# BQ25504.net
KiCad netlist of a schematic drawn in EAGLE
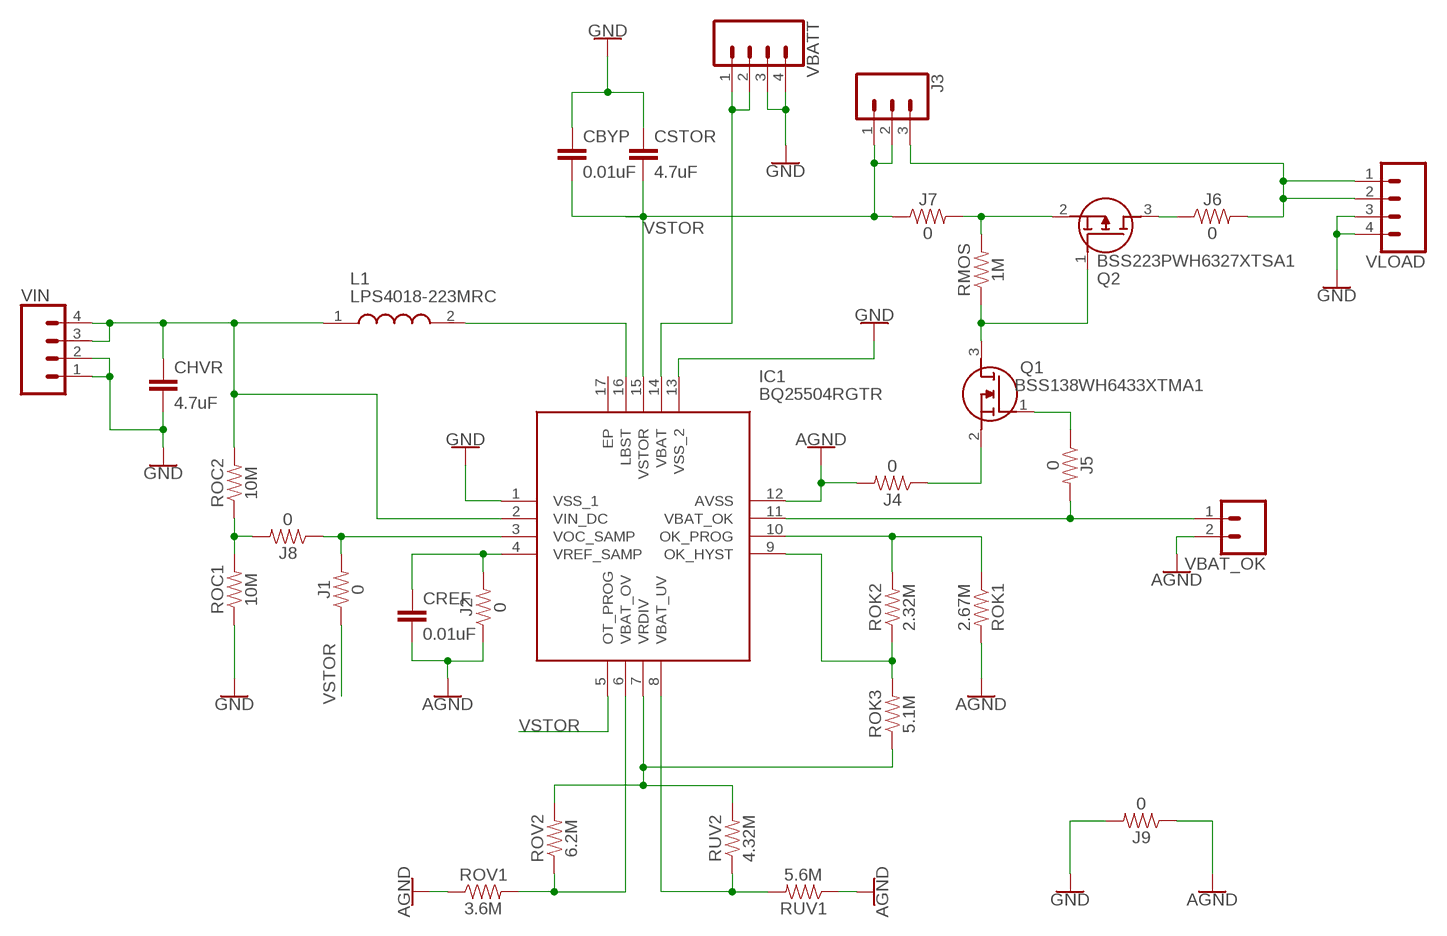
[diagram p0: schematic, sheet 1]

(export (version "E")
  (design (tool "Eeschema 10.0.6"))
  (components
    (comp (ref "CBYP")
      (value "0.01uF")
      (footprint "eagle-import:0603")
      (libsource (lib "eagle-import") (part "CAP-0603"))
    )
    (comp (ref "CHVR")
      (value "4.7uF")
      (footprint "eagle-import:0603")
      (libsource (lib "eagle-import") (part "CAP-0603"))
    )
    (comp (ref "CREF")
      (value "0.01uF")
      (footprint "eagle-import:0603")
      (libsource (lib "eagle-import") (part "CAP-0603"))
    )
    (comp (ref "CSTOR")
      (value "4.7uF")
      (footprint "eagle-import:0603")
      (libsource (lib "eagle-import") (part "CAP-0603"))
    )
    (comp (ref "IC1")
      (value "BQ25504RGTR")
      (footprint "eagle-import:QFN50P300X300X100-17N")
      (fields (field (name "MOUSER_PART_NUMBER") "595-BQ25504RGTR"))
      (libsource (lib "eagle-import") (part "BQ25504RGTR"))
    )
    (comp (ref "J1")
      (value "0")
      (footprint "eagle-import:0402")
      (libsource (lib "eagle-import") (part "RESISTOR0402"))
    )
    (comp (ref "J2")
      (value "0")
      (footprint "eagle-import:0402")
      (libsource (lib "eagle-import") (part "RESISTOR0402"))
    )
    (comp (ref "J3")
      (value "CONN_03")
      (footprint "eagle-import:1X03")
      (libsource (lib "eagle-import") (part "CONN_03"))
    )
    (comp (ref "J4")
      (value "0")
      (footprint "eagle-import:0402")
      (libsource (lib "eagle-import") (part "RESISTOR0402"))
    )
    (comp (ref "J5")
      (value "0")
      (footprint "eagle-import:0402")
      (libsource (lib "eagle-import") (part "RESISTOR0402"))
    )
    (comp (ref "J6")
      (value "0")
      (footprint "eagle-import:0402")
      (libsource (lib "eagle-import") (part "RESISTOR0402"))
    )
    (comp (ref "J7")
      (value "0")
      (footprint "eagle-import:0402")
      (libsource (lib "eagle-import") (part "RESISTOR0402"))
    )
    (comp (ref "J8")
      (value "0")
      (footprint "eagle-import:0402")
      (libsource (lib "eagle-import") (part "RESISTOR0402"))
    )
    (comp (ref "J9")
      (value "0")
      (footprint "eagle-import:0402")
      (libsource (lib "eagle-import") (part "RESISTOR0402"))
    )
    (comp (ref "L1")
      (value "LPS4018-223MRC")
      (footprint "eagle-import:LPS4018223MRC")
      (fields (field (name "MOUSER_PART_NUMBER") "994-LPS4018-223MRC"))
      (libsource (lib "eagle-import") (part "LPS4018-223MRC"))
    )
    (comp (ref "Q1")
      (value "BSS138WH6433XTMA1")
      (footprint "eagle-import:SOT65P210X100-3N")
      (fields (field (name "MOUSER_PART_NUMBER") "726-BSS138WH6433XTMA"))
      (libsource (lib "eagle-import") (part "BSS138WH6433XTMA1"))
    )
    (comp (ref "Q2")
      (value "BSS223PWH6327XTSA1")
      (footprint "eagle-import:SOT65P210X100-3N")
      (fields (field (name "MOUSER_PART_NUMBER") "726-BSS223PWH6327XTS"))
      (libsource (lib "eagle-import") (part "BSS223PWH6327XTSA1"))
    )
    (comp (ref "RMOS")
      (value "1M")
      (footprint "eagle-import:0603")
      (libsource (lib "eagle-import") (part "RESISTOR0603"))
    )
    (comp (ref "ROC1")
      (value "10M")
      (footprint "eagle-import:0603")
      (libsource (lib "eagle-import") (part "RESISTOR0603"))
    )
    (comp (ref "ROC2")
      (value "10M")
      (footprint "eagle-import:0603")
      (libsource (lib "eagle-import") (part "RESISTOR0603"))
    )
    (comp (ref "ROK1")
      (value "2.67M")
      (footprint "eagle-import:0603")
      (libsource (lib "eagle-import") (part "RESISTOR0603"))
    )
    (comp (ref "ROK2")
      (value "2.32M")
      (footprint "eagle-import:0603")
      (libsource (lib "eagle-import") (part "RESISTOR0603"))
    )
    (comp (ref "ROK3")
      (value "5.1M")
      (footprint "eagle-import:0603")
      (libsource (lib "eagle-import") (part "RESISTOR0603"))
    )
    (comp (ref "ROV1")
      (value "3.6M")
      (footprint "eagle-import:0603")
      (libsource (lib "eagle-import") (part "RESISTOR0603"))
    )
    (comp (ref "ROV2")
      (value "6.2M")
      (footprint "eagle-import:0603")
      (libsource (lib "eagle-import") (part "RESISTOR0603"))
    )
    (comp (ref "RUV1")
      (value "5.6M")
      (footprint "eagle-import:0603")
      (libsource (lib "eagle-import") (part "RESISTOR0603"))
    )
    (comp (ref "RUV2")
      (value "4.32M")
      (footprint "eagle-import:0603")
      (libsource (lib "eagle-import") (part "RESISTOR0603"))
    )
    (comp (ref "VBATT")
      (value "CONN_04PTH")
      (footprint "eagle-import:1X04")
      (libsource (lib "eagle-import") (part "CONN_04PTH"))
    )
    (comp (ref "VBAT_OK")
      (value "CONN_02")
      (footprint "eagle-import:1X02")
      (libsource (lib "eagle-import") (part "CONN_02"))
    )
    (comp (ref "VIN")
      (value "CONN_04PTH")
      (footprint "eagle-import:1X04")
      (libsource (lib "eagle-import") (part "CONN_04PTH"))
    )
    (comp (ref "VLOAD")
      (value "CONN_04PTH")
      (footprint "eagle-import:1X04")
      (libsource (lib "eagle-import") (part "CONN_04PTH"))
    )
  )
  (nets
    (net (code "1") (name "/VSTOR") (class "Default")
      (node (ref "CBYP") (pin "2") (pinfunction "2_2") (pintype "passive"))
      (node (ref "CSTOR") (pin "2") (pinfunction "2_2") (pintype "passive"))
      (node (ref "IC1") (pin "15") (pinfunction "VSTOR_15") (pintype "bidirectional"))
      (node (ref "IC1") (pin "5") (pinfunction "OT_PROG_5") (pintype "bidirectional"))
      (node (ref "J1") (pin "1") (pinfunction "1_1") (pintype "passive"))
      (node (ref "J3") (pin "1") (pinfunction "1_1") (pintype "passive"))
      (node (ref "J3") (pin "2") (pinfunction "2_2") (pintype "passive"))
      (node (ref "J7") (pin "1") (pinfunction "1_1") (pintype "passive"))
    )
    (net (code "2") (name "AGND") (class "Default")
      (node (ref "CREF") (pin "2") (pinfunction "2_2") (pintype "passive"))
      (node (ref "IC1") (pin "12") (pinfunction "AVSS_12") (pintype "bidirectional"))
      (node (ref "J2") (pin "1") (pinfunction "1_1") (pintype "passive"))
      (node (ref "J4") (pin "2") (pinfunction "2_2") (pintype "passive"))
      (node (ref "J9") (pin "1") (pinfunction "1_1") (pintype "passive"))
      (node (ref "ROK1") (pin "2") (pinfunction "2_2") (pintype "passive"))
      (node (ref "ROV1") (pin "1") (pinfunction "1_1") (pintype "passive"))
      (node (ref "RUV1") (pin "1") (pinfunction "1_1") (pintype "passive"))
      (node (ref "VBAT_OK") (pin "2") (pinfunction "2_2") (pintype "passive"))
    )
    (net (code "3") (name "GND") (class "Default")
      (node (ref "CBYP") (pin "1") (pinfunction "1_1") (pintype "passive"))
      (node (ref "CHVR") (pin "2") (pinfunction "2_2") (pintype "passive"))
      (node (ref "CSTOR") (pin "1") (pinfunction "1_1") (pintype "passive"))
      (node (ref "IC1") (pin "1") (pinfunction "VSS_1_1") (pintype "bidirectional"))
      (node (ref "IC1") (pin "13") (pinfunction "VSS_2_13") (pintype "bidirectional"))
      (node (ref "J9") (pin "2") (pinfunction "2_2") (pintype "passive"))
      (node (ref "ROC1") (pin "1") (pinfunction "1_1") (pintype "passive"))
      (node (ref "VBATT") (pin "3") (pinfunction "3_3") (pintype "passive"))
      (node (ref "VBATT") (pin "4") (pinfunction "4_4") (pintype "passive"))
      (node (ref "VIN") (pin "1") (pinfunction "1_1") (pintype "passive"))
      (node (ref "VIN") (pin "2") (pinfunction "2_2") (pintype "passive"))
      (node (ref "VLOAD") (pin "3") (pinfunction "3_3") (pintype "passive"))
      (node (ref "VLOAD") (pin "4") (pinfunction "4_4") (pintype "passive"))
    )
    (net (code "4") (name "Net-(IC1-LBST)") (class "Default")
      (node (ref "IC1") (pin "16") (pinfunction "LBST_16") (pintype "bidirectional"))
      (node (ref "L1") (pin "2") (pinfunction "2_2") (pintype "bidirectional"))
    )
    (net (code "5") (name "Net-(IC1-OK_HYST)") (class "Default")
      (node (ref "IC1") (pin "9") (pinfunction "OK_HYST_9") (pintype "bidirectional"))
      (node (ref "ROK2") (pin "1") (pinfunction "1_1") (pintype "passive"))
      (node (ref "ROK3") (pin "2") (pinfunction "2_2") (pintype "passive"))
    )
    (net (code "6") (name "Net-(IC1-OK_PROG)") (class "Default")
      (node (ref "IC1") (pin "10") (pinfunction "OK_PROG_10") (pintype "bidirectional"))
      (node (ref "ROK1") (pin "1") (pinfunction "1_1") (pintype "passive"))
      (node (ref "ROK2") (pin "2") (pinfunction "2_2") (pintype "passive"))
    )
    (net (code "7") (name "Net-(IC1-VBAT)") (class "Default")
      (node (ref "IC1") (pin "14") (pinfunction "VBAT_14") (pintype "bidirectional"))
      (node (ref "VBATT") (pin "1") (pinfunction "1_1") (pintype "passive"))
      (node (ref "VBATT") (pin "2") (pinfunction "2_2") (pintype "passive"))
    )
    (net (code "8") (name "Net-(IC1-VBAT_OK)") (class "Default")
      (node (ref "IC1") (pin "11") (pinfunction "VBAT_OK_11") (pintype "bidirectional"))
      (node (ref "J5") (pin "2") (pinfunction "2_2") (pintype "passive"))
      (node (ref "VBAT_OK") (pin "1") (pinfunction "1_1") (pintype "passive"))
    )
    (net (code "9") (name "Net-(IC1-VBAT_OV)") (class "Default")
      (node (ref "IC1") (pin "6") (pinfunction "VBAT_OV_6") (pintype "bidirectional"))
      (node (ref "ROV1") (pin "2") (pinfunction "2_2") (pintype "passive"))
      (node (ref "ROV2") (pin "1") (pinfunction "1_1") (pintype "passive"))
    )
    (net (code "10") (name "Net-(IC1-VBAT_UV)") (class "Default")
      (node (ref "IC1") (pin "8") (pinfunction "VBAT_UV_8") (pintype "bidirectional"))
      (node (ref "RUV1") (pin "2") (pinfunction "2_2") (pintype "passive"))
      (node (ref "RUV2") (pin "1") (pinfunction "1_1") (pintype "passive"))
    )
    (net (code "11") (name "Net-(IC1-VIN_DC)") (class "Default")
      (node (ref "CHVR") (pin "1") (pinfunction "1_1") (pintype "passive"))
      (node (ref "IC1") (pin "2") (pinfunction "VIN_DC_2") (pintype "bidirectional"))
      (node (ref "L1") (pin "1") (pinfunction "1_1") (pintype "bidirectional"))
      (node (ref "ROC2") (pin "2") (pinfunction "2_2") (pintype "passive"))
      (node (ref "VIN") (pin "3") (pinfunction "3_3") (pintype "passive"))
      (node (ref "VIN") (pin "4") (pinfunction "4_4") (pintype "passive"))
    )
    (net (code "12") (name "Net-(IC1-VOC_SAMP)") (class "Default")
      (node (ref "IC1") (pin "3") (pinfunction "VOC_SAMP_3") (pintype "bidirectional"))
      (node (ref "J1") (pin "2") (pinfunction "2_2") (pintype "passive"))
      (node (ref "J8") (pin "1") (pinfunction "1_1") (pintype "passive"))
    )
    (net (code "13") (name "Net-(IC1-VRDIV)") (class "Default")
      (node (ref "IC1") (pin "7") (pinfunction "VRDIV_7") (pintype "bidirectional"))
      (node (ref "ROK3") (pin "1") (pinfunction "1_1") (pintype "passive"))
      (node (ref "ROV2") (pin "2") (pinfunction "2_2") (pintype "passive"))
      (node (ref "RUV2") (pin "2") (pinfunction "2_2") (pintype "passive"))
    )
    (net (code "14") (name "Net-(IC1-VREF_SAMP)") (class "Default")
      (node (ref "CREF") (pin "1") (pinfunction "1_1") (pintype "passive"))
      (node (ref "IC1") (pin "4") (pinfunction "VREF_SAMP_4") (pintype "bidirectional"))
      (node (ref "J2") (pin "2") (pinfunction "2_2") (pintype "passive"))
    )
    (net (code "15") (name "Net-(J3-Pad3)") (class "Default")
      (node (ref "J3") (pin "3") (pinfunction "3_3") (pintype "passive"))
      (node (ref "J6") (pin "2") (pinfunction "2_2") (pintype "passive"))
      (node (ref "VLOAD") (pin "1") (pinfunction "1_1") (pintype "passive"))
      (node (ref "VLOAD") (pin "2") (pinfunction "2_2") (pintype "passive"))
    )
    (net (code "16") (name "Net-(J8-Pad2)") (class "Default")
      (node (ref "J8") (pin "2") (pinfunction "2_2") (pintype "passive"))
      (node (ref "ROC1") (pin "2") (pinfunction "2_2") (pintype "passive"))
      (node (ref "ROC2") (pin "1") (pinfunction "1_1") (pintype "passive"))
    )
    (net (code "17") (name "Net-(Q1-D)") (class "Default")
      (node (ref "Q1") (pin "3") (pinfunction "D_3") (pintype "bidirectional"))
      (node (ref "Q2") (pin "1") (pinfunction "G_1") (pintype "input"))
      (node (ref "RMOS") (pin "1") (pinfunction "1_1") (pintype "passive"))
    )
    (net (code "18") (name "Net-(Q1-G)") (class "Default")
      (node (ref "J5") (pin "1") (pinfunction "1_1") (pintype "passive"))
      (node (ref "Q1") (pin "1") (pinfunction "G_1") (pintype "bidirectional"))
    )
    (net (code "19") (name "Net-(Q1-S)") (class "Default")
      (node (ref "J4") (pin "1") (pinfunction "1_1") (pintype "passive"))
      (node (ref "Q1") (pin "2") (pinfunction "S_2") (pintype "bidirectional"))
    )
    (net (code "20") (name "Net-(Q2-D)") (class "Default")
      (node (ref "J6") (pin "1") (pinfunction "1_1") (pintype "passive"))
      (node (ref "Q2") (pin "3") (pinfunction "D_3") (pintype "bidirectional"))
    )
    (net (code "21") (name "Net-(Q2-S)") (class "Default")
      (node (ref "J7") (pin "2") (pinfunction "2_2") (pintype "passive"))
      (node (ref "Q2") (pin "2") (pinfunction "S_2") (pintype "bidirectional"))
      (node (ref "RMOS") (pin "2") (pinfunction "2_2") (pintype "passive"))
    )
    (net (code "22") (name "unconnected-(IC1-EP-Pad17)") (class "Default")
      (node (ref "IC1") (pin "17") (pinfunction "EP_17") (pintype "bidirectional"))
    )
  )
)
